# 5V_Regulator.net
KiCad netlist of a schematic drawn in Altium Designer
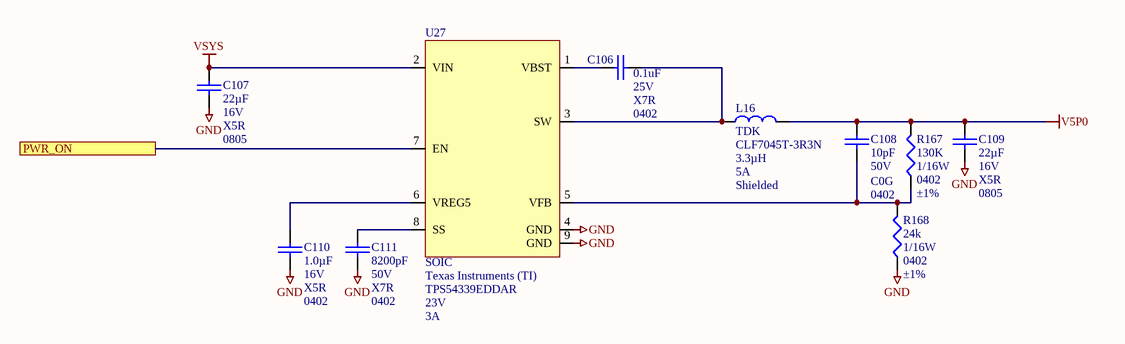
[diagram p0: 5V Regulator.SchDoc]

(export (version "E")
  (design (tool "Eeschema 10.0.6"))
  (components
    (comp (ref "C106")
      (value "C_0402_0.1UF_25V")
      (footprint "C_0402")
      (description "CAP CER 0.1UF 25V X6S 0402")
      (fields
        (field (name "TOLERANCE") "10%")
        (field (name "CAPACITANCE") "0.1uF")
        (field (name "VOLTAGE - RATED") "25V")
        (field (name "TEMPERATURE COEFFICIENT") "X7R")
        (field (name "PACKAGE / CASE") "0402")
      )
      (libsource (lib "Cospan Design") (part "C_0402_0.1UF_25V"))
    )
    (comp (ref "C107")
      (value "22µF")
      (footprint "C_0805")
      (description "CAP CER 22UF 16V 10% X5R 0805")
      (fields
        (field (name "TOLERANCE") "20%")
        (field (name "CAPACITANCE") "22µF")
        (field (name "VOLTAGE - RATED") "16V")
        (field (name "TEMPERATURE COEFFICIENT") "X5R")
        (field (name "PACKAGE / CASE") "0805")
      )
      (libsource (lib "Main Library") (part "C_0805_22µF_16V"))
    )
    (comp (ref "C108")
      (value "10pF")
      (footprint "C_0402")
      (description "CAP CER 10PF 50V NP0 0402")
      (fields
        (field (name "MANUFACTURER") "Taiyo Yuden")
        (field (name "MANUFACTURER PART NUMBER") "UMK105CG100DV-F")
        (field (name "CAPACITANCE") "10pF")
        (field (name "VOLTAGE - RATED") "50V")
        (field (name "TEMPERATURE COEFFICIENT") "C0G")
        (field (name "PACKAGE / CASE") "0402")
      )
      (libsource (lib "Main Library") (part "C_0402_10PF_50V"))
    )
    (comp (ref "C109")
      (value "22µF")
      (footprint "C_0805")
      (description "CAP CER 22UF 16V 10% X5R 0805")
      (fields
        (field (name "TOLERANCE") "20%")
        (field (name "CAPACITANCE") "22µF")
        (field (name "VOLTAGE - RATED") "16V")
        (field (name "TEMPERATURE COEFFICIENT") "X5R")
        (field (name "PACKAGE / CASE") "0805")
      )
      (libsource (lib "Main Library") (part "C_0805_22µF_16V"))
    )
    (comp (ref "C110")
      (value "1.0uF")
      (footprint "C_0402")
      (description "CAP CER 1.0UF 16V X5R 0402")
      (fields
        (field (name "TOLERANCE") "10%")
        (field (name "CAPACITANCE") "1.0µF")
        (field (name "VOLTAGE - RATED") "16V")
        (field (name "TEMPERATURE COEFFICIENT") "X5R")
        (field (name "PACKAGE / CASE") "0402")
        (field (name "VOLTAGE") "16V")
      )
      (libsource (lib "Main LibraryX") (part "C_0402_1.0UF_16V"))
    )
    (comp (ref "C111")
      (value "C_0402_8.2NF")
      (footprint "C_ERA-0402")
      (description "CAP CER 8200PF 50V X7R 0402")
      (fields
        (field (name "TOLERANCE") "10%")
        (field (name "CAPACITANCE") "8200pF")
        (field (name "VOLTAGE - RATED") "50V")
        (field (name "TEMPERATURE COEFFICIENT") "X7R")
        (field (name "PACKAGE / CASE") "0402")
        (field (name "VOLTAGE") "50V")
      )
      (libsource (lib "Cospan Design") (part "C_0402_8.2NF"))
    )
    (comp (ref "L16")
      (value "L_CLF7045T-3R3N")
      (footprint "CLF7045")
      (description "FIXED IND 15UH 1.9A 95.8 MOHM")
      (fields
        (field (name "MANUFACTURER") "TDK")
        (field (name "MANUFACTURER PART NUMBER") "CLF7045T-3R3N")
        (field (name "INDUCTANCE") "3.3µH")
        (field (name "CURRENT RATING") "5A")
        (field (name "SHIELDING") "Shielded")
        (field (name "TOLERANCE") "±30%")
      )
      (libsource (lib "Cospan Design") (part "L_CLF7045T-3R3N"))
    )
    (comp (ref "R167")
      (value "R_0402_130K")
      (footprint "R_0402")
      (description "RES 130K OHM 1/10W 1% 0402 SMD")
      (fields
        (field (name "MANUFACTURER") "Panasonic Electronic Components")
        (field (name "MANUFACTURER PART NUMBER") "ERJ-2RKF1303X")
        (field (name "RESISTANCE IN OHMS") "130K")
        (field (name "POWER (WATTS)") "1/16W")
        (field (name "CASE") "0402")
        (field (name "TOLERANCE") "±1%")
      )
      (libsource (lib "Main Library") (part "R_0402_130K"))
    )
    (comp (ref "R168")
      (value "R_0402_24k")
      (footprint "R_0402")
      (description "RES SMD 24K OHM 1% 1/16W 0402")
      (fields
        (field (name "MANUFACTURER") "Yageo")
        (field (name "MANUFACTURER PART NUMBER") "RC0402FR-0724KL")
        (field (name "RESISTANCE IN OHMS") "24k")
        (field (name "POWER (WATTS)") "1/16W")
        (field (name "CASE") "0402")
        (field (name "TOLERANCE") "±1%")
      )
      (libsource (lib "Cospan Design") (part "R_0402_24k"))
    )
    (comp (ref "U27")
      (value "U_TPS54339EDDAR")
      (footprint "DDA0008E")
      (description "IC REG BUCK SYNC ADJ 3A 8SOPWR")
      (fields
        (field (name "CASE/PACKAGE") "SOIC")
        (field (name "MANUFACTURER") "Texas Instruments (TI)")
        (field (name "MANUFACTURER PART NUMBER") "TPS54339EDDAR")
        (field (name "MAX INPUT VOLTAGE") "23V")
        (field (name "OUTPUT CURRENT") "3A")
      )
      (libsource (lib "Cospan Design") (part "U_TPS54339EDDAR"))
    )
  )
  (nets
    (net (code "1") (name "/PWR_ON") (class "Default")
      (node (ref "U27") (pin "7") (pinfunction "EN_7") (pintype "passive"))
    )
    (net (code "2") (name "GND") (class "Default")
      (node (ref "C107") (pin "1") (pinfunction "1_1") (pintype "passive"))
      (node (ref "C109") (pin "1") (pinfunction "1_1") (pintype "passive"))
      (node (ref "C110") (pin "1") (pinfunction "1_1") (pintype "passive"))
      (node (ref "C111") (pin "1") (pinfunction "1_1") (pintype "passive"))
      (node (ref "R168") (pin "2") (pinfunction "2_2") (pintype "passive"))
      (node (ref "U27") (pin "4") (pinfunction "GND_4") (pintype "passive"))
      (node (ref "U27") (pin "9") (pinfunction "GND_9") (pintype "passive"))
    )
    (net (code "3") (name "Net-(U27-SS)") (class "Default")
      (node (ref "C111") (pin "2") (pinfunction "2_2") (pintype "passive"))
      (node (ref "U27") (pin "8") (pinfunction "SS_8") (pintype "passive"))
    )
    (net (code "4") (name "Net-(U27-SW)") (class "Default")
      (node (ref "C106") (pin "1") (pinfunction "1_1") (pintype "passive"))
      (node (ref "L16") (pin "2") (pintype "passive"))
      (node (ref "U27") (pin "3") (pinfunction "SW_3") (pintype "passive"))
    )
    (net (code "5") (name "Net-(U27-VBST)") (class "Default")
      (node (ref "C106") (pin "2") (pinfunction "2_2") (pintype "passive"))
      (node (ref "U27") (pin "1") (pinfunction "VBST_1") (pintype "passive"))
    )
    (net (code "6") (name "Net-(U27-VFB)") (class "Default")
      (node (ref "C108") (pin "1") (pinfunction "1_1") (pintype "passive"))
      (node (ref "R167") (pin "2") (pinfunction "2_2") (pintype "passive"))
      (node (ref "R168") (pin "1") (pinfunction "1_1") (pintype "passive"))
      (node (ref "U27") (pin "5") (pinfunction "VFB_5") (pintype "passive"))
    )
    (net (code "7") (name "Net-(U27-VREG5)") (class "Default")
      (node (ref "C110") (pin "2") (pinfunction "2_2") (pintype "passive"))
      (node (ref "U27") (pin "6") (pinfunction "VREG5_6") (pintype "passive"))
    )
    (net (code "8") (name "V5P0") (class "Default")
      (node (ref "C108") (pin "2") (pinfunction "2_2") (pintype "passive"))
      (node (ref "C109") (pin "2") (pinfunction "2_2") (pintype "passive"))
      (node (ref "L16") (pin "1") (pintype "passive"))
      (node (ref "R167") (pin "1") (pinfunction "1_1") (pintype "passive"))
    )
    (net (code "9") (name "VSYS") (class "Default")
      (node (ref "C107") (pin "2") (pinfunction "2_2") (pintype "passive"))
      (node (ref "U27") (pin "2") (pinfunction "VIN_2") (pintype "passive"))
    )
  )
)
